# SuperBot_Sheet_main.net
KiCad netlist of a schematic drawn in Altium Designer
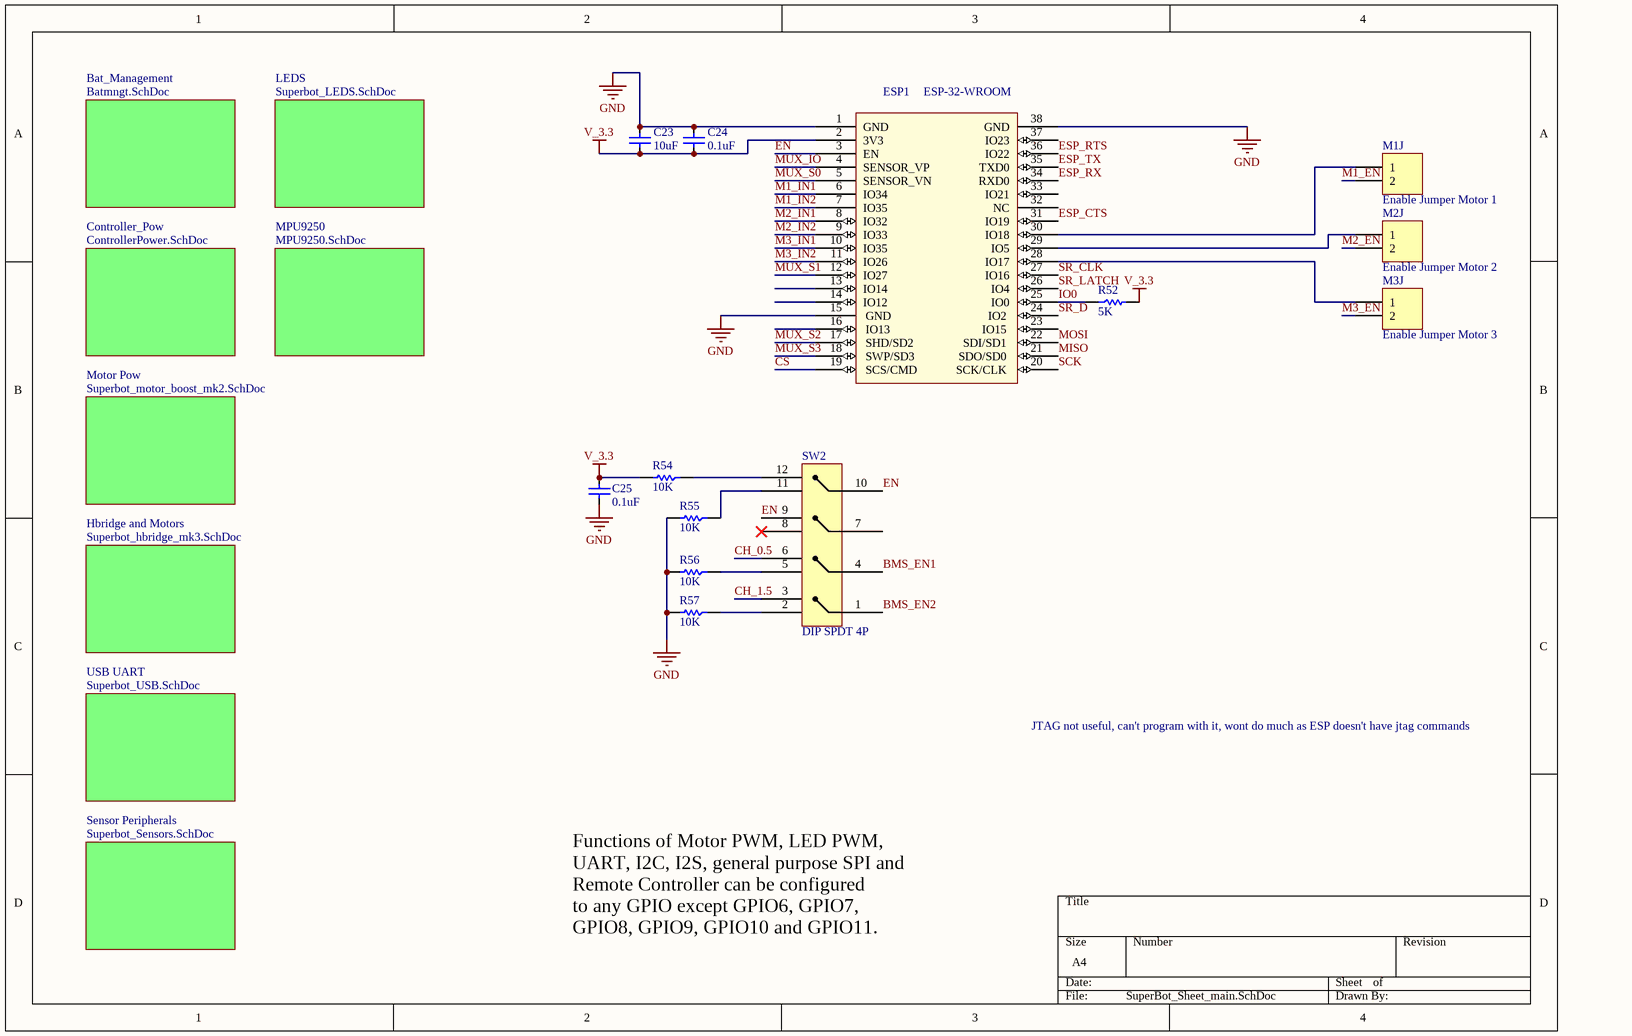
[diagram p0: SuperBot_Sheet_main.SchDoc]

(export (version "E")
  (design (tool "Eeschema 10.0.6"))
  (components
    (comp (ref "C23")
      (value "10uF")
      (footprint "CAP0603R")
      (description "Capacitor")
      (fields
        (field (name "MANUFACTURER") "Microchip Technology")
        (field (name "MANUFACTURER PART NUM") "MIC5378YC5-TR")
      )
      (libsource (lib "SuperBot_Schlib1") (part "C"))
    )
    (comp (ref "C24")
      (value "0.1uF")
      (footprint "CAP0603R")
      (description "Capacitor")
      (fields
        (field (name "MANUFACTURER") "Microchip Technology")
        (field (name "MANUFACTURER PART NUM") "MIC5378YC5-TR")
      )
      (libsource (lib "SuperBot_Schlib1") (part "C"))
    )
    (comp (ref "C25")
      (value "0.1uF")
      (footprint "CAP0603R")
      (description "Capacitor")
      (fields
        (field (name "MANUFACTURER") "Microchip Technology")
        (field (name "MANUFACTURER PART NUM") "MIC5378YC5-TR")
      )
      (libsource (lib "SuperBot_Schlib1") (part "C"))
    )
    (comp (ref "ESP1")
      (value "ESP-32-WROOM")
      (footprint "ESP-32-WROOM")
      (description "ESP-32-WROOM, WIFI + BT")
      (libsource (lib "SuperBot_Schlib1") (part "ESP-32-WROOM"))
    )
    (comp (ref "M1J")
      (value "Enable Jumper Motor 1")
      (footprint "HDR1X2")
      (description "Header, 2-Pin")
      (fields (field (name "PUBLISHER") "Altium Limited"))
      (libsource (lib "Miscellaneous Connectors") (part "Header 2"))
    )
    (comp (ref "M2J")
      (value "Enable Jumper Motor 2")
      (footprint "HDR1X2")
      (description "Header, 2-Pin")
      (fields (field (name "PUBLISHER") "Altium Limited"))
      (libsource (lib "Miscellaneous Connectors") (part "Header 2"))
    )
    (comp (ref "M3J")
      (value "Enable Jumper Motor 3")
      (footprint "HDR1X2")
      (description "Header, 2-Pin")
      (fields (field (name "PUBLISHER") "Altium Limited"))
      (libsource (lib "Miscellaneous Connectors") (part "Header 2"))
    )
    (comp (ref "R52")
      (value "5K")
      (footprint "RES0603R")
      (description "Resistor")
      (libsource (lib "SuperBot_Schlib1") (part "R"))
    )
    (comp (ref "R54")
      (value "10K")
      (footprint "RES0603R")
      (description "Resistor")
      (libsource (lib "SuperBot_Schlib1") (part "R"))
    )
    (comp (ref "R55")
      (value "10K")
      (footprint "RES0603R")
      (description "Resistor")
      (libsource (lib "SuperBot_Schlib1") (part "R"))
    )
    (comp (ref "R56")
      (value "10K")
      (footprint "RES0603R")
      (description "Resistor")
      (libsource (lib "SuperBot_Schlib1") (part "R"))
    )
    (comp (ref "R57")
      (value "10K")
      (footprint "RES0603R")
      (description "Resistor")
      (libsource (lib "SuperBot_Schlib1") (part "R"))
    )
    (comp (ref "SW2")
      (value "DIP SPDT 4P")
      (footprint "DIP SPDT 4P")
      (libsource (lib "SuperBot_Schlib1") (part "DIP SPDT 4P"))
    )
  )
  (nets
    (net (code "1") (name "/BMS_EN1") (class "Default") (node (ref "SW2") (pin "4") (pintype "passive")))
    (net (code "2") (name "/BMS_EN2") (class "Default") (node (ref "SW2") (pin "1") (pintype "passive")))
    (net (code "3") (name "/CH_0.5") (class "Default") (node (ref "SW2") (pin "6") (pintype "passive")))
    (net (code "4") (name "/CH_1.5") (class "Default") (node (ref "SW2") (pin "3") (pintype "passive")))
    (net (code "5") (name "/CS") (class "Default")
      (node (ref "ESP1") (pin "19") (pinfunction "SCS/CMD_19") (pintype "bidirectional"))
    )
    (net (code "6") (name "/EN") (class "Default")
      (node (ref "ESP1") (pin "3") (pinfunction "EN_3") (pintype "passive"))
      (node (ref "SW2") (pin "10") (pintype "passive"))
      (node (ref "SW2") (pin "9") (pintype "passive"))
    )
    (net (code "7") (name "/ESP_CTS") (class "Default")
      (node (ref "ESP1") (pin "31") (pinfunction "IO19_31") (pintype "bidirectional"))
    )
    (net (code "8") (name "/ESP_RTS") (class "Default")
      (node (ref "ESP1") (pin "36") (pinfunction "IO22_36") (pintype "bidirectional"))
    )
    (net (code "9") (name "/ESP_RX") (class "Default")
      (node (ref "ESP1") (pin "34") (pinfunction "RXD0_34") (pintype "bidirectional"))
    )
    (net (code "10") (name "/ESP_TX") (class "Default")
      (node (ref "ESP1") (pin "35") (pinfunction "TXD0_35") (pintype "bidirectional"))
    )
    (net (code "11") (name "/IO0") (class "Default")
      (node (ref "ESP1") (pin "25") (pinfunction "IO0_25") (pintype "bidirectional"))
      (node (ref "R52") (pin "1") (pintype "passive"))
    )
    (net (code "12") (name "/M1_EN") (class "Default")
      (node (ref "M1J") (pin "2") (pinfunction "2_2") (pintype "passive"))
    )
    (net (code "13") (name "/M1_IN1") (class "Default")
      (node (ref "ESP1") (pin "6") (pinfunction "IO34_6") (pintype "passive"))
    )
    (net (code "14") (name "/M1_IN2") (class "Default")
      (node (ref "ESP1") (pin "7") (pinfunction "IO35_7") (pintype "passive"))
    )
    (net (code "15") (name "/M2_EN") (class "Default")
      (node (ref "M2J") (pin "2") (pinfunction "2_2") (pintype "passive"))
    )
    (net (code "16") (name "/M2_IN1") (class "Default")
      (node (ref "ESP1") (pin "8") (pinfunction "IO32_8") (pintype "bidirectional"))
    )
    (net (code "17") (name "/M2_IN2") (class "Default")
      (node (ref "ESP1") (pin "9") (pinfunction "IO33_9") (pintype "bidirectional"))
    )
    (net (code "18") (name "/M3_EN") (class "Default")
      (node (ref "M3J") (pin "2") (pinfunction "2_2") (pintype "passive"))
    )
    (net (code "19") (name "/M3_IN1") (class "Default")
      (node (ref "ESP1") (pin "10") (pinfunction "IO35_10") (pintype "bidirectional"))
    )
    (net (code "20") (name "/M3_IN2") (class "Default")
      (node (ref "ESP1") (pin "11") (pinfunction "IO26_11") (pintype "bidirectional"))
    )
    (net (code "21") (name "/MISO") (class "Default")
      (node (ref "ESP1") (pin "21") (pinfunction "SDO/SD0_21") (pintype "bidirectional"))
    )
    (net (code "22") (name "/MOSI") (class "Default")
      (node (ref "ESP1") (pin "22") (pinfunction "SDI/SD1_22") (pintype "bidirectional"))
    )
    (net (code "23") (name "/MUX_IO") (class "Default")
      (node (ref "ESP1") (pin "4") (pinfunction "SENSOR_VP_4") (pintype "passive"))
    )
    (net (code "24") (name "/MUX_S0") (class "Default")
      (node (ref "ESP1") (pin "5") (pinfunction "SENSOR_VN_5") (pintype "passive"))
    )
    (net (code "25") (name "/MUX_S1") (class "Default")
      (node (ref "ESP1") (pin "12") (pinfunction "IO27_12") (pintype "bidirectional"))
    )
    (net (code "26") (name "/MUX_S2") (class "Default")
      (node (ref "ESP1") (pin "17") (pinfunction "SHD/SD2_17") (pintype "bidirectional"))
    )
    (net (code "27") (name "/MUX_S3") (class "Default")
      (node (ref "ESP1") (pin "18") (pinfunction "SWP/SD3_18") (pintype "bidirectional"))
    )
    (net (code "28") (name "/SCK") (class "Default")
      (node (ref "ESP1") (pin "20") (pinfunction "SCK/CLK_20") (pintype "bidirectional"))
    )
    (net (code "29") (name "/SR_CLK") (class "Default")
      (node (ref "ESP1") (pin "27") (pinfunction "IO16_27") (pintype "bidirectional"))
    )
    (net (code "30") (name "/SR_D") (class "Default")
      (node (ref "ESP1") (pin "24") (pinfunction "IO2_24") (pintype "bidirectional"))
    )
    (net (code "31") (name "/SR_LATCH") (class "Default")
      (node (ref "ESP1") (pin "26") (pinfunction "IO4_26") (pintype "bidirectional"))
    )
    (net (code "32") (name "GND") (class "Default")
      (node (ref "C23") (pin "1") (pinfunction "1_1") (pintype "passive"))
      (node (ref "C24") (pin "1") (pinfunction "1_1") (pintype "passive"))
      (node (ref "C25") (pin "2") (pinfunction "2_2") (pintype "passive"))
      (node (ref "ESP1") (pin "1") (pinfunction "GND_1") (pintype "passive"))
      (node (ref "ESP1") (pin "15") (pinfunction "GND_15") (pintype "passive"))
      (node (ref "ESP1") (pin "38") (pinfunction "GND_38") (pintype "passive"))
      (node (ref "R55") (pin "2") (pintype "passive"))
      (node (ref "R56") (pin "2") (pintype "passive"))
      (node (ref "R57") (pin "2") (pintype "passive"))
    )
    (net (code "33") (name "Net-(ESP1-IO5)") (class "Default")
      (node (ref "ESP1") (pin "29") (pinfunction "IO5_29") (pintype "bidirectional"))
      (node (ref "M2J") (pin "1") (pinfunction "1_1") (pintype "passive"))
    )
    (net (code "34") (name "Net-(ESP1-IO17)") (class "Default")
      (node (ref "ESP1") (pin "28") (pinfunction "IO17_28") (pintype "bidirectional"))
      (node (ref "M3J") (pin "1") (pinfunction "1_1") (pintype "passive"))
    )
    (net (code "35") (name "Net-(ESP1-IO18)") (class "Default")
      (node (ref "ESP1") (pin "30") (pinfunction "IO18_30") (pintype "bidirectional"))
      (node (ref "M1J") (pin "1") (pinfunction "1_1") (pintype "passive"))
    )
    (net (code "36") (name "Net-(R54-Pad1)") (class "Default")
      (node (ref "R54") (pin "1") (pintype "passive"))
      (node (ref "SW2") (pin "12") (pintype "passive"))
    )
    (net (code "37") (name "Net-(R55-Pad1)") (class "Default")
      (node (ref "R55") (pin "1") (pintype "passive"))
      (node (ref "SW2") (pin "11") (pintype "passive"))
    )
    (net (code "38") (name "Net-(R56-Pad1)") (class "Default")
      (node (ref "R56") (pin "1") (pintype "passive"))
      (node (ref "SW2") (pin "5") (pintype "passive"))
    )
    (net (code "39") (name "Net-(R57-Pad1)") (class "Default")
      (node (ref "R57") (pin "1") (pintype "passive"))
      (node (ref "SW2") (pin "2") (pintype "passive"))
    )
    (net (code "40") (name "V_3.3") (class "Default")
      (node (ref "C23") (pin "2") (pinfunction "2_2") (pintype "passive"))
      (node (ref "C24") (pin "2") (pinfunction "2_2") (pintype "passive"))
      (node (ref "C25") (pin "1") (pinfunction "1_1") (pintype "passive"))
      (node (ref "ESP1") (pin "2") (pinfunction "3V3_2") (pintype "passive"))
      (node (ref "R52") (pin "2") (pintype "passive"))
      (node (ref "R54") (pin "2") (pintype "passive"))
    )
    (net (code "41") (name "unconnected-(ESP1-IO12-Pad14)") (class "Default")
      (node (ref "ESP1") (pin "14") (pinfunction "IO12_14") (pintype "bidirectional"))
    )
    (net (code "42") (name "unconnected-(ESP1-IO13-Pad16)") (class "Default")
      (node (ref "ESP1") (pin "16") (pinfunction "IO13_16") (pintype "bidirectional"))
    )
    (net (code "43") (name "unconnected-(ESP1-IO14-Pad13)") (class "Default")
      (node (ref "ESP1") (pin "13") (pinfunction "IO14_13") (pintype "bidirectional"))
    )
    (net (code "44") (name "unconnected-(ESP1-IO15-Pad23)") (class "Default")
      (node (ref "ESP1") (pin "23") (pinfunction "IO15_23") (pintype "bidirectional"))
    )
    (net (code "45") (name "unconnected-(ESP1-IO21-Pad33)") (class "Default")
      (node (ref "ESP1") (pin "33") (pinfunction "IO21_33") (pintype "bidirectional"))
    )
    (net (code "46") (name "unconnected-(ESP1-IO23-Pad37)") (class "Default")
      (node (ref "ESP1") (pin "37") (pinfunction "IO23_37") (pintype "bidirectional"))
    )
    (net (code "47") (name "unconnected-(ESP1-NC-Pad32)") (class "Default")
      (node (ref "ESP1") (pin "32") (pinfunction "NC_32") (pintype "passive"))
    )
    (net (code "48") (name "unconnected-(SW2-Pad7)") (class "Default")
      (node (ref "SW2") (pin "7") (pintype "passive"))
    )
    (net (code "49") (name "unconnected-(SW2-Pad8)") (class "Default")
      (node (ref "SW2") (pin "8") (pintype "passive+no_connect"))
    )
  )
)
